# edge_dff_clk_high.net
KiCad netlist of a schematic drawn in Altium Designer
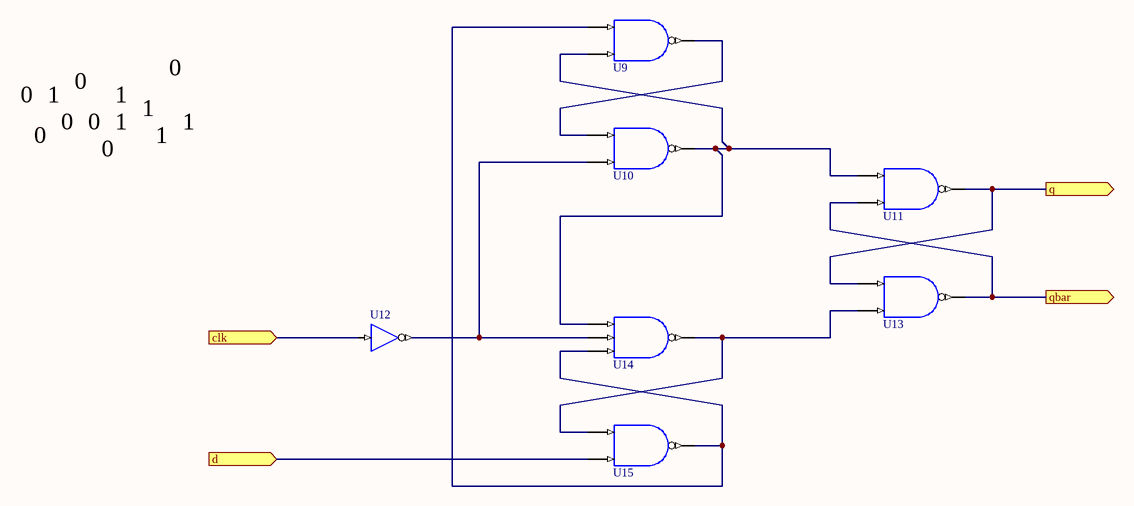
[diagram p0: edge_dff_clk_high.SchDoc]

(export (version "E")
  (design (tool "Eeschema 10.0.6"))
  (components
    (comp (ref "U9")
      (value "AND 2")
      (description "2 Input AND")
      (libsource (lib "BlockSchematics") (part "AND_2"))
    )
    (comp (ref "U10")
      (value "AND 2")
      (description "2 Input AND")
      (libsource (lib "BlockSchematics") (part "AND_2"))
    )
    (comp (ref "U11")
      (value "AND 2")
      (description "2 Input AND")
      (libsource (lib "BlockSchematics") (part "AND_2"))
    )
    (comp (ref "U12")
      (value "BUF_inv")
      (description "1-bit General Purpose (Non-inverting) Buffer")
      (libsource (lib "BlockSchematics") (part "BUF_inv"))
    )
    (comp (ref "U13")
      (value "AND 2")
      (description "2 Input AND")
      (libsource (lib "BlockSchematics") (part "AND_2"))
    )
    (comp (ref "U14")
      (value "NAND_3")
      (description "3 Input NAND 1 Not")
      (libsource (lib "BlockSchematics") (part "NAND_3"))
    )
    (comp (ref "U15")
      (value "AND 2")
      (description "2 Input AND")
      (libsource (lib "BlockSchematics") (part "AND_2"))
    )
  )
  (nets
    (net (code "1") (name "/clk") (class "Default")
      (node (ref "U12") (pin "I") (pinfunction "I_I") (pintype "input"))
    )
    (net (code "2") (name "/d") (class "Default")
      (node (ref "U15") (pin "B") (pinfunction "B_B") (pintype "input"))
    )
    (net (code "3") (name "/q") (class "Default")
      (node (ref "U11") (pin "Y") (pinfunction "Y_Y") (pintype "output"))
      (node (ref "U13") (pin "A") (pinfunction "A_A") (pintype "input"))
    )
    (net (code "4") (name "/qbar") (class "Default")
      (node (ref "U11") (pin "B") (pinfunction "B_B") (pintype "input"))
      (node (ref "U13") (pin "Y") (pinfunction "Y_Y") (pintype "output"))
    )
    (net (code "5") (name "Net-(U10-PadA)") (class "Default")
      (node (ref "U10") (pin "A") (pinfunction "A_A") (pintype "input"))
      (node (ref "U9") (pin "Y") (pinfunction "Y_Y") (pintype "output"))
    )
    (net (code "6") (name "Net-(U10-PadB)") (class "Default")
      (node (ref "U10") (pin "B") (pinfunction "B_B") (pintype "input"))
      (node (ref "U12") (pin "O") (pinfunction "O_O") (pintype "output"))
      (node (ref "U14") (pin "B") (pinfunction "B_B") (pintype "input"))
    )
    (net (code "7") (name "Net-(U10-PadY)") (class "Default")
      (node (ref "U10") (pin "Y") (pinfunction "Y_Y") (pintype "output"))
      (node (ref "U11") (pin "A") (pinfunction "A_A") (pintype "input"))
      (node (ref "U14") (pin "A") (pinfunction "A_A") (pintype "input"))
      (node (ref "U9") (pin "B") (pinfunction "B_B") (pintype "input"))
    )
    (net (code "8") (name "Net-(U13-PadB)") (class "Default")
      (node (ref "U13") (pin "B") (pinfunction "B_B") (pintype "input"))
      (node (ref "U14") (pin "Y") (pinfunction "Y_Y") (pintype "output"))
      (node (ref "U15") (pin "A") (pinfunction "A_A") (pintype "input"))
    )
    (net (code "9") (name "Net-(U14-PadC)") (class "Default")
      (node (ref "U14") (pin "C") (pinfunction "C_C") (pintype "input"))
      (node (ref "U15") (pin "Y") (pinfunction "Y_Y") (pintype "output"))
      (node (ref "U9") (pin "A") (pinfunction "A_A") (pintype "input"))
    )
  )
)
